# shiftRegister.net
KiCad netlist of a schematic drawn in Altium Designer
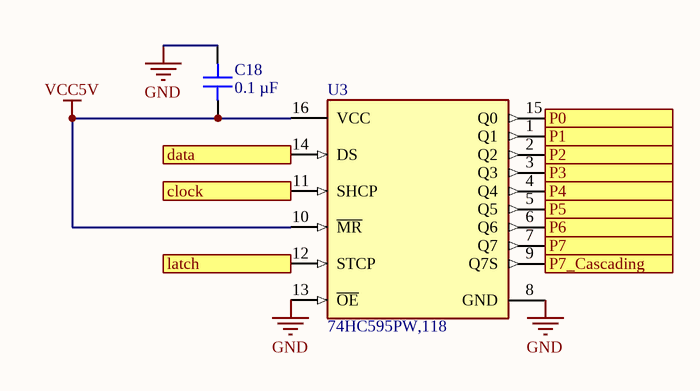
[diagram p0: shiftRegister.SchDoc]

(export (version "E")
  (design (tool "Eeschema 10.0.6"))
  (components
    (comp (ref "C18")
      (value "0.1 µF")
      (footprint "CAP 0603_1608")
      (description "CAP CER 0.1UF 50V X7R 0603")
      (fields (field (name "PART NUMBER") "C0603C104K5RAC7411") (field (name "MANUFACTURER") "KEMET"))
      (libsource (lib "Celestial Altium Library - altium_library") (part "Capacitor"))
    )
    (comp (ref "U3")
      (value "74HC595PW,118")
      (footprint "FP-SOT403-1-MFG")
      (description "IC SHIFT REGISTER 8BIT 16TSSOP")
      (libsource (lib "Altium Content Vault") (part "27683e23285b137cd268a0f18c66bed"))
    )
  )
  (nets
    (net (code "1") (name "/P0") (class "Default")
      (node (ref "U3") (pin "15") (pinfunction "Q0_15") (pintype "output"))
    )
    (net (code "2") (name "/P1") (class "Default")
      (node (ref "U3") (pin "1") (pinfunction "Q1_1") (pintype "output"))
    )
    (net (code "3") (name "/P2") (class "Default")
      (node (ref "U3") (pin "2") (pinfunction "Q2_2") (pintype "output"))
    )
    (net (code "4") (name "/P3") (class "Default")
      (node (ref "U3") (pin "3") (pinfunction "Q3_3") (pintype "output"))
    )
    (net (code "5") (name "/P4") (class "Default")
      (node (ref "U3") (pin "4") (pinfunction "Q4_4") (pintype "output"))
    )
    (net (code "6") (name "/P5") (class "Default")
      (node (ref "U3") (pin "5") (pinfunction "Q5_5") (pintype "output"))
    )
    (net (code "7") (name "/P6") (class "Default")
      (node (ref "U3") (pin "6") (pinfunction "Q6_6") (pintype "output"))
    )
    (net (code "8") (name "/P7") (class "Default")
      (node (ref "U3") (pin "7") (pinfunction "Q7_7") (pintype "output"))
    )
    (net (code "9") (name "/P7_Cascading") (class "Default")
      (node (ref "U3") (pin "9") (pinfunction "Q7S_9") (pintype "output"))
    )
    (net (code "10") (name "/clock") (class "Default")
      (node (ref "U3") (pin "11") (pinfunction "SHCP_11") (pintype "input"))
    )
    (net (code "11") (name "/data") (class "Default")
      (node (ref "U3") (pin "14") (pinfunction "DS_14") (pintype "input"))
    )
    (net (code "12") (name "/latch") (class "Default")
      (node (ref "U3") (pin "12") (pinfunction "STCP_12") (pintype "input"))
    )
    (net (code "13") (name "GND") (class "Default")
      (node (ref "C18") (pin "2") (pinfunction "2_2") (pintype "passive"))
      (node (ref "U3") (pin "13") (pinfunction "~{OE}_13") (pintype "input"))
      (node (ref "U3") (pin "8") (pinfunction "GND_8") (pintype "power_in"))
    )
    (net (code "14") (name "VCC5V") (class "Default")
      (node (ref "C18") (pin "1") (pinfunction "1_1") (pintype "passive"))
      (node (ref "U3") (pin "10") (pinfunction "~{MR}_10") (pintype "input"))
      (node (ref "U3") (pin "16") (pinfunction "VCC_16") (pintype "power_in"))
    )
  )
)
